# ESP32_Weather.net
KiCad netlist of a schematic drawn in Altium Designer
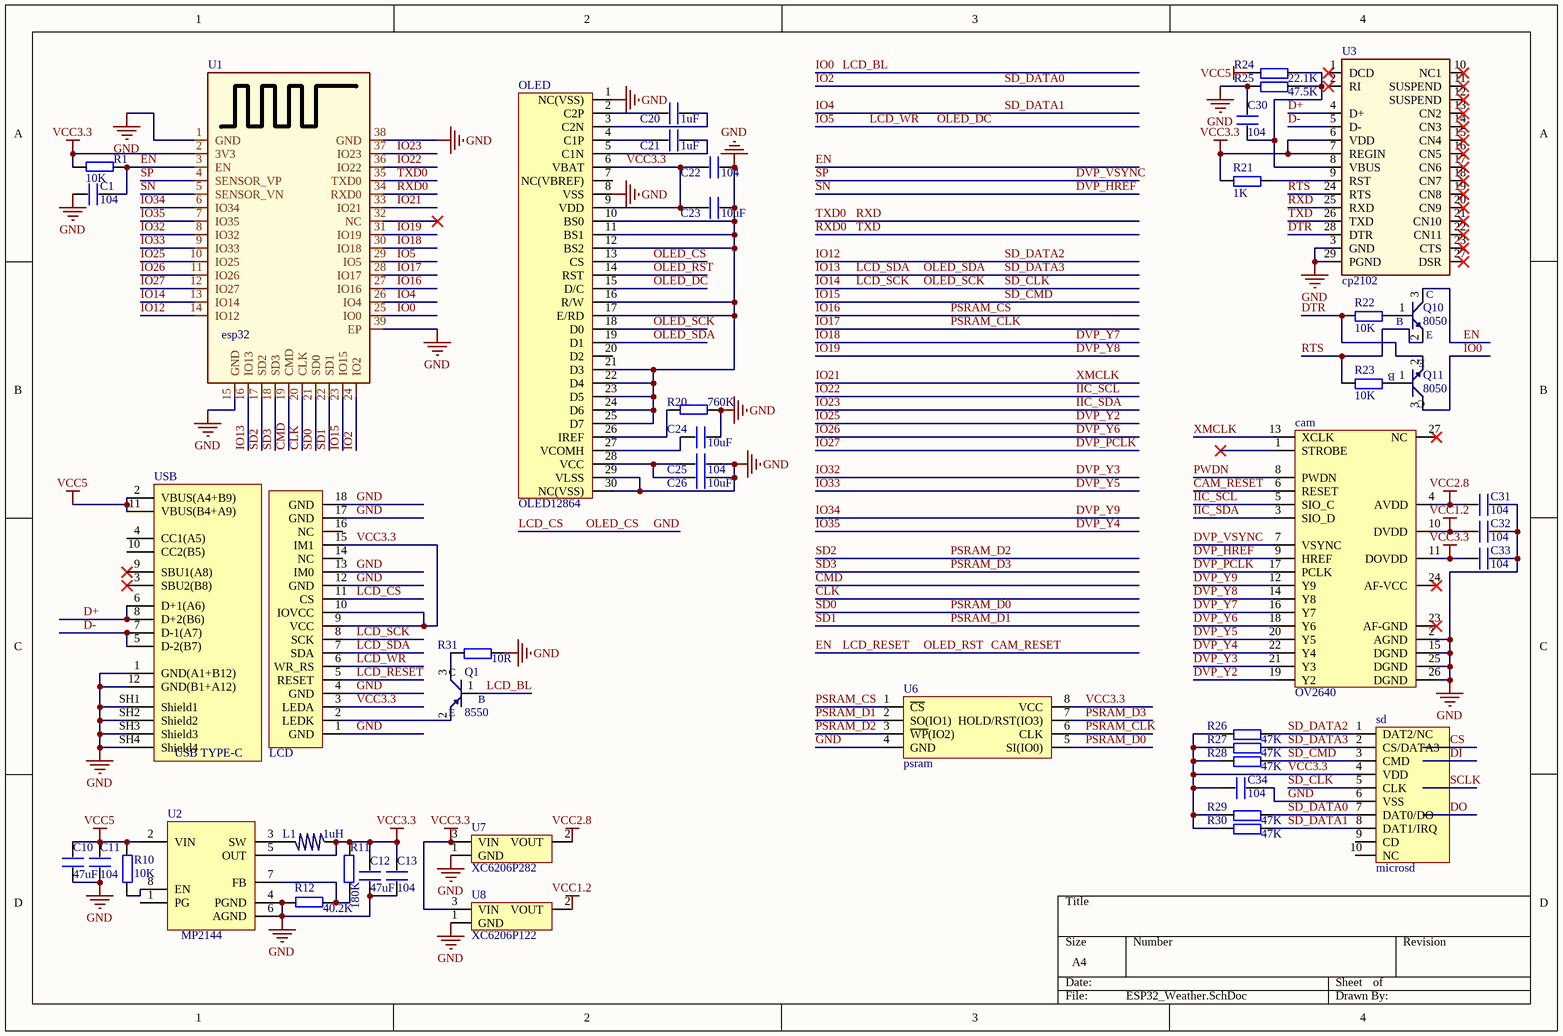
[diagram p0: ESP32_Weather.SchDoc]

(export (version "E")
  (design (tool "Eeschema 10.0.6"))
  (components
    (comp (ref "C1")
      (value "104")
      (footprint "C 0603_L")
      (libsource (lib "WarShip V3 STM32103封装库") (part "C"))
    )
    (comp (ref "C10")
      (value "47uF")
      (footprint "C 0805_L")
      (libsource (lib "WarShip V3 STM32103封装库") (part "C"))
    )
    (comp (ref "C11")
      (value "104")
      (footprint "C 0603_L")
      (libsource (lib "WarShip V3 STM32103封装库") (part "C"))
    )
    (comp (ref "C12")
      (value "47uF")
      (footprint "C 0805_L")
      (libsource (lib "WarShip V3 STM32103封装库") (part "C"))
    )
    (comp (ref "C13")
      (value "104")
      (footprint "C 0603_L")
      (libsource (lib "WarShip V3 STM32103封装库") (part "C"))
    )
    (comp (ref "C20")
      (value "1uF")
      (footprint "C 0603_L")
      (libsource (lib "WarShip V3 STM32103封装库") (part "C"))
    )
    (comp (ref "C21")
      (value "1uF")
      (footprint "C 0603_L")
      (libsource (lib "WarShip V3 STM32103封装库") (part "C"))
    )
    (comp (ref "C22")
      (value "104")
      (footprint "C 0603_L")
      (libsource (lib "WarShip V3 STM32103封装库") (part "C"))
    )
    (comp (ref "C23")
      (value "10uF")
      (footprint "C 0603_L")
      (libsource (lib "WarShip V3 STM32103封装库") (part "C"))
    )
    (comp (ref "C24")
      (value "10uF")
      (footprint "C 0603_L")
      (libsource (lib "WarShip V3 STM32103封装库") (part "C"))
    )
    (comp (ref "C25")
      (value "104")
      (footprint "C 0603_L")
      (libsource (lib "WarShip V3 STM32103封装库") (part "C"))
    )
    (comp (ref "C26")
      (value "10uF")
      (footprint "C 0603_L")
      (libsource (lib "WarShip V3 STM32103封装库") (part "C"))
    )
    (comp (ref "C30")
      (value "104")
      (footprint "C 0603_L")
      (libsource (lib "WarShip V3 STM32103封装库") (part "C"))
    )
    (comp (ref "C31")
      (value "104")
      (footprint "C 0603_L")
      (libsource (lib "WarShip V3 STM32103封装库") (part "C"))
    )
    (comp (ref "C32")
      (value "104")
      (footprint "C 0603_L")
      (libsource (lib "WarShip V3 STM32103封装库") (part "C"))
    )
    (comp (ref "C33")
      (value "104")
      (footprint "C 0603_L")
      (libsource (lib "WarShip V3 STM32103封装库") (part "C"))
    )
    (comp (ref "C34")
      (value "104")
      (footprint "C 0603_L")
      (libsource (lib "WarShip V3 STM32103封装库") (part "C"))
    )
    (comp (ref "cam")
      (value "OV2640")
      (footprint "OV5640")
      (libsource (lib "stm32f767igt6simple") (part "OV5640"))
    )
    (comp (ref "L1") (value "1uH") (footprint "NR3015") (libsource (lib "MiniFly ") (part "L")))
    (comp (ref "LCD")
      (value "LCD-TFT-H13TS38A")
      (footprint "TFT-H13TS43B")
      (description "LCD,TFT,1.3'240*240,禹龙")
      (libsource (lib "Pandora_STM32L4_Board_V2.4") (part "LCD-TFT-H13TS38A"))
    )
    (comp (ref "OLED")
      (value "OLED12864")
      (footprint "OLED_0.96")
      (libsource (lib "OLED模块封装库") (part "OLED12864"))
    )
    (comp (ref "Q1") (value "8550") (footprint "SOT23-3L") (libsource (lib "ESP32_Weather") (part "8550PNP")))
    (comp (ref "Q10")
      (value "8050")
      (footprint "SOT23-3L")
      (libsource (lib "ESP32_Weather") (part "8050NPN"))
    )
    (comp (ref "Q11")
      (value "8050")
      (footprint "SOT23-3L")
      (libsource (lib "ESP32_Weather") (part "8050NPN"))
    )
    (comp (ref "R1") (value "10K") (footprint "R 0603_L") (libsource (lib "阿波罗STM32F4&F7底板封装库") (part "R")))
    (comp (ref "R10") (value "10K") (footprint "R 0603_L") (libsource (lib "阿波罗STM32F4&F7底板封装库") (part "R")))
    (comp (ref "R11") (value "180K") (footprint "R 0603_L") (libsource (lib "电阻-电容-电感") (part "R")))
    (comp (ref "R12") (value "40.2K") (footprint "R 0603_L") (libsource (lib "电阻-电容-电感") (part "R")))
    (comp (ref "R20")
      (value "760K")
      (footprint "R 0603_L")
      (libsource (lib "WarShip V3 STM32103封装库") (part "R"))
    )
    (comp (ref "R21")
      (value "1K")
      (footprint "R 0603_L")
      (libsource (lib "WarShip V3 STM32103封装库") (part "R"))
    )
    (comp (ref "R22")
      (value "10K")
      (footprint "R 0603_L")
      (libsource (lib "WarShip V3 STM32103封装库") (part "R"))
    )
    (comp (ref "R23")
      (value "10K")
      (footprint "R 0603_L")
      (libsource (lib "WarShip V3 STM32103封装库") (part "R"))
    )
    (comp (ref "R24")
      (value "22.1K")
      (footprint "R 0603_L")
      (libsource (lib "WarShip V3 STM32103封装库") (part "R"))
    )
    (comp (ref "R25")
      (value "47.5K")
      (footprint "R 0603_L")
      (libsource (lib "WarShip V3 STM32103封装库") (part "R"))
    )
    (comp (ref "R26")
      (value "47K")
      (footprint "R 0603_L")
      (libsource (lib "WarShip V3 STM32103封装库") (part "R"))
    )
    (comp (ref "R27")
      (value "47K")
      (footprint "R 0603_L")
      (libsource (lib "WarShip V3 STM32103封装库") (part "R"))
    )
    (comp (ref "R28")
      (value "47K")
      (footprint "R 0603_L")
      (libsource (lib "WarShip V3 STM32103封装库") (part "R"))
    )
    (comp (ref "R29")
      (value "47K")
      (footprint "R 0603_L")
      (libsource (lib "WarShip V3 STM32103封装库") (part "R"))
    )
    (comp (ref "R30")
      (value "47K")
      (footprint "R 0603_L")
      (libsource (lib "WarShip V3 STM32103封装库") (part "R"))
    )
    (comp (ref "R31")
      (value "10R")
      (footprint "R 0603_L")
      (libsource (lib "WarShip V3 STM32103封装库") (part "R"))
    )
    (comp (ref "sd")
      (value "microsd")
      (footprint "microsd3")
      (libsource (lib "stm32f767igt6simple") (part "microsd"))
    )
    (comp (ref "U1") (value "esp32") (footprint "ESP32") (libsource (lib "ESP32_Weather") (part "ESP32")))
    (comp (ref "U2") (value "MP2144") (footprint "SOT23-8L") (libsource (lib "LDO和DCDC") (part "MP2144")))
    (comp (ref "U3")
      (value "cp2102")
      (footprint "QFN28 5x5_N")
      (libsource (lib "ESP32_Weather") (part "CP2102"))
    )
    (comp (ref "U6")
      (value "psram")
      (footprint "SOP8_L")
      (libsource (lib "stm32f767igt6simple") (part "w25q256"))
    )
    (comp (ref "U7")
      (value "XC6206P282")
      (footprint "SOT23-3L")
      (description "LDO,SOT23,1.2~5.0V")
      (libsource (lib "ATK-OV5640摄像头模块封装库") (part "XC6206"))
    )
    (comp (ref "U8")
      (value "XC6206P122")
      (footprint "SOT23-3L")
      (description "LDO,SOT23,1.2~5.0V")
      (libsource (lib "ATK-OV5640摄像头模块封装库") (part "XC6206"))
    )
    (comp (ref "USB")
      (value "USB TypeC")
      (footprint "USB Type-C")
      (description "12P TypeC 母座")
      (libsource (lib "接口类") (part "USB Type-C"))
    )
  )
  (nets
    (net (code "1") (name "/CAM_RESET") (class "Default")
      (node (ref "C1") (pin "2") (pintype "passive"))
      (node (ref "LCD") (pin "5") (pinfunction "RESET_5") (pintype "passive"))
      (node (ref "OLED") (pin "14") (pinfunction "RST_14") (pintype "passive"))
      (node (ref "Q10") (pin "3") (pinfunction "C_3") (pintype "passive"))
      (node (ref "R1") (pin "1") (pintype "passive"))
      (node (ref "U1") (pin "3") (pinfunction "EN_3") (pintype "passive"))
      (node (ref "cam") (pin "6") (pinfunction "RESET_6") (pintype "passive"))
    )
    (net (code "2") (name "/CLK") (class "Default")
      (node (ref "U1") (pin "20") (pinfunction "CLK_20") (pintype "passive"))
    )
    (net (code "3") (name "/CMD") (class "Default")
      (node (ref "U1") (pin "19") (pinfunction "CMD_19") (pintype "passive"))
    )
    (net (code "5") (name "/D+") (class "Default")
      (node (ref "U3") (pin "4") (pinfunction "D+_4") (pintype "passive"))
      (node (ref "USB") (pin "6") (pinfunction "D+1(A6)_6") (pintype "passive"))
      (node (ref "USB") (pin "8") (pinfunction "D+2(B6)_8") (pintype "passive"))
    )
    (net (code "6") (name "/D-") (class "Default")
      (node (ref "U3") (pin "5") (pinfunction "D-_5") (pintype "passive"))
      (node (ref "USB") (pin "5") (pinfunction "D-2(B7)_5") (pintype "passive"))
      (node (ref "USB") (pin "7") (pinfunction "D-1(A7)_7") (pintype "passive"))
    )
    (net (code "9") (name "/DTR") (class "Default")
      (node (ref "Q11") (pin "2") (pinfunction "E_2") (pintype "passive"))
      (node (ref "R22") (pin "1") (pintype "passive"))
      (node (ref "U3") (pin "28") (pinfunction "DTR_28") (pintype "passive"))
    )
    (net (code "10") (name "/DVP_HREF") (class "Default")
      (node (ref "U1") (pin "5") (pinfunction "SENSOR_VN_5") (pintype "passive"))
      (node (ref "cam") (pin "9") (pinfunction "HREF_9") (pintype "passive"))
    )
    (net (code "11") (name "/DVP_PCLK") (class "Default")
      (node (ref "U1") (pin "12") (pinfunction "IO27_12") (pintype "passive"))
      (node (ref "cam") (pin "17") (pinfunction "PCLK_17") (pintype "passive"))
    )
    (net (code "12") (name "/DVP_VSYNC") (class "Default")
      (node (ref "U1") (pin "4") (pinfunction "SENSOR_VP_4") (pintype "passive"))
      (node (ref "cam") (pin "7") (pinfunction "VSYNC_7") (pintype "passive"))
    )
    (net (code "13") (name "/DVP_Y2") (class "Default")
      (node (ref "U1") (pin "10") (pinfunction "IO25_10") (pintype "passive"))
      (node (ref "cam") (pin "19") (pinfunction "Y2_19") (pintype "passive"))
    )
    (net (code "14") (name "/DVP_Y3") (class "Default")
      (node (ref "U1") (pin "8") (pinfunction "IO32_8") (pintype "passive"))
      (node (ref "cam") (pin "21") (pinfunction "Y3_21") (pintype "passive"))
    )
    (net (code "15") (name "/DVP_Y4") (class "Default")
      (node (ref "U1") (pin "7") (pinfunction "IO35_7") (pintype "passive"))
      (node (ref "cam") (pin "22") (pinfunction "Y4_22") (pintype "passive"))
    )
    (net (code "16") (name "/DVP_Y5") (class "Default")
      (node (ref "U1") (pin "9") (pinfunction "IO33_9") (pintype "passive"))
      (node (ref "cam") (pin "20") (pinfunction "Y5_20") (pintype "passive"))
    )
    (net (code "17") (name "/DVP_Y6") (class "Default")
      (node (ref "U1") (pin "11") (pinfunction "IO26_11") (pintype "passive"))
      (node (ref "cam") (pin "18") (pinfunction "Y6_18") (pintype "passive"))
    )
    (net (code "18") (name "/DVP_Y7") (class "Default")
      (node (ref "U1") (pin "30") (pinfunction "IO18_30") (pintype "passive"))
      (node (ref "cam") (pin "16") (pinfunction "Y7_16") (pintype "passive"))
    )
    (net (code "19") (name "/DVP_Y8") (class "Default")
      (node (ref "U1") (pin "31") (pinfunction "IO19_31") (pintype "passive"))
      (node (ref "cam") (pin "14") (pinfunction "Y8_14") (pintype "passive"))
    )
    (net (code "20") (name "/DVP_Y9") (class "Default")
      (node (ref "U1") (pin "6") (pinfunction "IO34_6") (pintype "passive"))
      (node (ref "cam") (pin "12") (pinfunction "Y9_12") (pintype "passive"))
    )
    (net (code "21") (name "/IIC_SCL") (class "Default")
      (node (ref "U1") (pin "36") (pinfunction "IO22_36") (pintype "passive"))
      (node (ref "cam") (pin "5") (pinfunction "SIO_C_5") (pintype "passive"))
    )
    (net (code "22") (name "/IIC_SDA") (class "Default")
      (node (ref "U1") (pin "37") (pinfunction "IO23_37") (pintype "passive"))
      (node (ref "cam") (pin "3") (pinfunction "SIO_D_3") (pintype "passive"))
    )
    (net (code "23") (name "/IO0") (class "Default")
      (node (ref "Q1") (pin "1") (pinfunction "B_1") (pintype "passive"))
      (node (ref "Q11") (pin "3") (pinfunction "C_3") (pintype "passive"))
      (node (ref "U1") (pin "25") (pinfunction "IO0_25") (pintype "passive"))
    )
    (net (code "24") (name "/IO2") (class "Default")
      (node (ref "R29") (pin "2") (pintype "passive"))
      (node (ref "U1") (pin "24") (pinfunction "IO2_24") (pintype "passive"))
      (node (ref "sd") (pin "7") (pinfunction "DAT0/DO_7") (pintype "passive"))
    )
    (net (code "25") (name "/IO4") (class "Default")
      (node (ref "R30") (pin "2") (pintype "passive"))
      (node (ref "U1") (pin "26") (pinfunction "IO4_26") (pintype "passive"))
      (node (ref "sd") (pin "8") (pinfunction "DAT1/IRQ_8") (pintype "passive"))
    )
    (net (code "26") (name "/IO5") (class "Default")
      (node (ref "LCD") (pin "6") (pinfunction "WR_RS_6") (pintype "passive"))
      (node (ref "OLED") (pin "15") (pinfunction "D/C_15") (pintype "passive"))
      (node (ref "U1") (pin "29") (pinfunction "IO5_29") (pintype "passive"))
    )
    (net (code "27") (name "/IO12") (class "Default")
      (node (ref "R26") (pin "2") (pintype "passive"))
      (node (ref "U1") (pin "14") (pinfunction "IO12_14") (pintype "passive"))
      (node (ref "sd") (pin "1") (pinfunction "DAT2/NC_1") (pintype "passive"))
    )
    (net (code "28") (name "/IO13") (class "Default")
      (node (ref "LCD") (pin "7") (pinfunction "SDA_7") (pintype "passive"))
      (node (ref "OLED") (pin "19") (pinfunction "D1_19") (pintype "passive"))
      (node (ref "R27") (pin "2") (pintype "passive"))
      (node (ref "U1") (pin "16") (pinfunction "IO13_16") (pintype "passive"))
      (node (ref "sd") (pin "2") (pinfunction "CS/DATA3_2") (pintype "passive"))
    )
    (net (code "29") (name "/IO14") (class "Default")
      (node (ref "LCD") (pin "8") (pinfunction "SCK_8") (pintype "passive"))
      (node (ref "OLED") (pin "18") (pinfunction "D0_18") (pintype "passive"))
      (node (ref "U1") (pin "13") (pinfunction "IO14_13") (pintype "passive"))
      (node (ref "sd") (pin "5") (pinfunction "CLK_5") (pintype "passive"))
    )
    (net (code "30") (name "/IO15") (class "Default")
      (node (ref "R28") (pin "2") (pintype "passive"))
      (node (ref "U1") (pin "23") (pinfunction "IO15_23") (pintype "passive"))
      (node (ref "sd") (pin "3") (pinfunction "CMD_3") (pintype "passive"))
    )
    (net (code "31") (name "/IO16") (class "Default")
      (node (ref "U1") (pin "27") (pinfunction "IO16_27") (pintype "passive"))
      (node (ref "U6") (pin "1") (pinfunction "~{CS}_1") (pintype "passive"))
    )
    (net (code "32") (name "/IO17") (class "Default")
      (node (ref "U1") (pin "28") (pinfunction "IO17_28") (pintype "passive"))
      (node (ref "U6") (pin "6") (pinfunction "CLK_6") (pintype "passive"))
    )
    (net (code "33") (name "/IO21") (class "Default")
      (node (ref "U1") (pin "33") (pinfunction "IO21_33") (pintype "passive"))
      (node (ref "cam") (pin "13") (pinfunction "XCLK_13") (pintype "passive"))
    )
    (net (code "34") (name "/PSRAM_D0") (class "Default")
      (node (ref "U1") (pin "21") (pinfunction "SD0_21") (pintype "passive"))
      (node (ref "U6") (pin "5") (pinfunction "SI(IO0)_5") (pintype "power_in"))
    )
    (net (code "35") (name "/PSRAM_D1") (class "Default")
      (node (ref "U1") (pin "22") (pinfunction "SD1_22") (pintype "passive"))
      (node (ref "U6") (pin "2") (pinfunction "SO(IO1)_2") (pintype "passive"))
    )
    (net (code "36") (name "/PSRAM_D2") (class "Default")
      (node (ref "U1") (pin "17") (pinfunction "SD2_17") (pintype "passive"))
      (node (ref "U6") (pin "3") (pinfunction "~{WP}(IO2)_3") (pintype "passive"))
    )
    (net (code "37") (name "/PSRAM_D3") (class "Default")
      (node (ref "U1") (pin "18") (pinfunction "SD3_18") (pintype "passive"))
      (node (ref "U6") (pin "7") (pinfunction "HOLD/RST(IO3)_7") (pintype "power_in"))
    )
    (net (code "38") (name "/PWDN") (class "Default")
      (node (ref "cam") (pin "8") (pinfunction "PWDN_8") (pintype "passive"))
    )
    (net (code "39") (name "/RTS") (class "Default")
      (node (ref "Q10") (pin "2") (pinfunction "E_2") (pintype "passive"))
      (node (ref "R23") (pin "1") (pintype "passive"))
      (node (ref "U3") (pin "24") (pinfunction "RTS_24") (pintype "passive"))
    )
    (net (code "40") (name "/RXD") (class "Default")
      (node (ref "U1") (pin "35") (pinfunction "TXD0_35") (pintype "passive"))
      (node (ref "U3") (pin "25") (pinfunction "RXD_25") (pintype "passive"))
    )
    (net (code "41") (name "/RXD0") (class "Default")
      (node (ref "U1") (pin "34") (pinfunction "RXD0_34") (pintype "passive"))
      (node (ref "U3") (pin "26") (pinfunction "TXD_26") (pintype "passive"))
    )
    (net (code "43") (name "GND") (class "Default")
      (node (ref "C1") (pin "1") (pintype "passive"))
      (node (ref "C10") (pin "1") (pintype "passive"))
      (node (ref "C11") (pin "1") (pintype "passive"))
      (node (ref "C12") (pin "1") (pintype "passive"))
      (node (ref "C13") (pin "1") (pintype "passive"))
      (node (ref "C22") (pin "1") (pintype "passive"))
      (node (ref "C23") (pin "1") (pintype "passive"))
      (node (ref "C24") (pin "1") (pintype "passive"))
      (node (ref "C25") (pin "1") (pintype "passive"))
      (node (ref "C26") (pin "1") (pintype "passive"))
      (node (ref "C30") (pin "1") (pintype "passive"))
      (node (ref "C31") (pin "2") (pintype "passive"))
      (node (ref "C32") (pin "2") (pintype "passive"))
      (node (ref "C33") (pin "2") (pintype "passive"))
      (node (ref "C34") (pin "2") (pintype "passive"))
      (node (ref "LCD") (pin "1") (pinfunction "GND_1") (pintype "passive"))
      (node (ref "LCD") (pin "11") (pinfunction "CS_11") (pintype "passive"))
      (node (ref "LCD") (pin "12") (pinfunction "GND_12") (pintype "passive"))
      (node (ref "LCD") (pin "13") (pinfunction "IM0_13") (pintype "passive"))
      (node (ref "LCD") (pin "17") (pinfunction "GND_17") (pintype "passive"))
      (node (ref "LCD") (pin "18") (pinfunction "GND_18") (pintype "passive"))
      (node (ref "LCD") (pin "4") (pinfunction "GND_4") (pintype "passive"))
      (node (ref "OLED") (pin "1") (pinfunction "NC(VSS)_1") (pintype "passive"))
      (node (ref "OLED") (pin "10") (pinfunction "BS0_10") (pintype "passive"))
      (node (ref "OLED") (pin "11") (pinfunction "BS1_11") (pintype "passive"))
      (node (ref "OLED") (pin "12") (pinfunction "BS2_12") (pintype "passive"))
      (node (ref "OLED") (pin "13") (pinfunction "CS_13") (pintype "passive"))
      (node (ref "OLED") (pin "16") (pinfunction "R/W_16") (pintype "passive"))
      (node (ref "OLED") (pin "17") (pinfunction "E/RD_17") (pintype "passive"))
      (node (ref "OLED") (pin "21") (pinfunction "D3_21") (pintype "passive"))
      (node (ref "OLED") (pin "22") (pinfunction "D4_22") (pintype "passive"))
      (node (ref "OLED") (pin "23") (pinfunction "D5_23") (pintype "passive"))
      (node (ref "OLED") (pin "24") (pinfunction "D6_24") (pintype "passive"))
      (node (ref "OLED") (pin "25") (pinfunction "D7_25") (pintype "passive"))
      (node (ref "OLED") (pin "29") (pinfunction "VLSS_29") (pintype "passive"))
      (node (ref "OLED") (pin "30") (pinfunction "NC(VSS)_30") (pintype "passive"))
      (node (ref "OLED") (pin "8") (pinfunction "VSS_8") (pintype "passive"))
      (node (ref "R12") (pin "2") (pintype "passive"))
      (node (ref "R20") (pin "1") (pintype "passive"))
      (node (ref "R25") (pin "1") (pintype "passive"))
      (node (ref "R31") (pin "2") (pintype "passive"))
      (node (ref "U1") (pin "1") (pinfunction "GND_1") (pintype "passive"))
      (node (ref "U1") (pin "15") (pinfunction "GND_15") (pintype "passive"))
      (node (ref "U1") (pin "38") (pinfunction "GND_38") (pintype "passive"))
      (node (ref "U1") (pin "39") (pinfunction "EP_39") (pintype "passive"))
      (node (ref "U2") (pin "4") (pinfunction "PGND_4") (pintype "passive"))
      (node (ref "U2") (pin "6") (pinfunction "AGND_6") (pintype "passive"))
      (node (ref "U3") (pin "29") (pinfunction "PGND_29") (pintype "passive"))
      (node (ref "U3") (pin "3") (pinfunction "GND_3") (pintype "passive"))
      (node (ref "U6") (pin "4") (pinfunction "GND_4") (pintype "passive"))
      (node (ref "U7") (pin "1") (pinfunction "GND_1") (pintype "passive"))
      (node (ref "U8") (pin "1") (pinfunction "GND_1") (pintype "passive"))
      (node (ref "USB") (pin "1") (pinfunction "GND(A1+B12)_1") (pintype "passive"))
      (node (ref "USB") (pin "12") (pinfunction "GND(B1+A12)_12") (pintype "passive"))
      (node (ref "USB") (pin "SH1") (pinfunction "Shield1_SH1") (pintype "passive"))
      (node (ref "USB") (pin "SH2") (pinfunction "Shield2_SH2") (pintype "passive"))
      (node (ref "USB") (pin "SH3") (pinfunction "Shield3_SH3") (pintype "passive"))
      (node (ref "USB") (pin "SH4") (pinfunction "Shield4_SH4") (pintype "passive"))
      (node (ref "cam") (pin "15") (pinfunction "DGND_15") (pintype "passive"))
      (node (ref "cam") (pin "2") (pinfunction "AGND_2") (pintype "passive"))
      (node (ref "cam") (pin "25") (pinfunction "DGND_25") (pintype "passive"))
      (node (ref "cam") (pin "26") (pinfunction "DGND_26") (pintype "passive"))
      (node (ref "sd") (pin "6") (pinfunction "VSS_6") (pintype "passive"))
    )
    (net (code "44") (name "Net-(LCD-LEDK)") (class "Default")
      (node (ref "LCD") (pin "2") (pinfunction "LEDK_2") (pintype "passive"))
      (node (ref "Q1") (pin "2") (pinfunction "E_2") (pintype "passive"))
    )
    (net (code "45") (name "Net-(OLED-C1N)") (class "Default")
      (node (ref "C21") (pin "1") (pintype "passive"))
      (node (ref "OLED") (pin "5") (pinfunction "C1N_5") (pintype "passive"))
    )
    (net (code "46") (name "Net-(OLED-C1P)") (class "Default")
      (node (ref "C21") (pin "2") (pintype "passive"))
      (node (ref "OLED") (pin "4") (pinfunction "C1P_4") (pintype "passive"))
    )
    (net (code "47") (name "Net-(OLED-C2N)") (class "Default")
      (node (ref "C20") (pin "1") (pintype "passive"))
      (node (ref "OLED") (pin "3") (pinfunction "C2N_3") (pintype "passive"))
    )
    (net (code "48") (name "Net-(OLED-C2P)") (class "Default")
      (node (ref "C20") (pin "2") (pintype "passive"))
      (node (ref "OLED") (pin "2") (pinfunction "C2P_2") (pintype "passive"))
    )
    (net (code "49") (name "Net-(OLED-IREF)") (class "Default")
      (node (ref "OLED") (pin "26") (pinfunction "IREF_26") (pintype "passive"))
      (node (ref "R20") (pin "2") (pintype "passive"))
    )
    (net (code "50") (name "Net-(OLED-VCC)") (class "Default")
      (node (ref "C25") (pin "2") (pintype "passive"))
      (node (ref "C26") (pin "2") (pintype "passive"))
      (node (ref "OLED") (pin "28") (pinfunction "VCC_28") (pintype "passive"))
    )
    (net (code "51") (name "Net-(OLED-VCOMH)") (class "Default")
      (node (ref "C24") (pin "2") (pintype "passive"))
      (node (ref "OLED") (pin "27") (pinfunction "VCOMH_27") (pintype "passive"))
    )
    (net (code "52") (name "Net-(Q1-C)") (class "Default")
      (node (ref "Q1") (pin "3") (pinfunction "C_3") (pintype "passive"))
      (node (ref "R31") (pin "1") (pintype "passive"))
    )
    (net (code "53") (name "Net-(Q10-B)") (class "Default")
      (node (ref "Q10") (pin "1") (pinfunction "B_1") (pintype "passive"))
      (node (ref "R22") (pin "2") (pintype "passive"))
    )
    (net (code "54") (name "Net-(Q11-B)") (class "Default")
      (node (ref "Q11") (pin "1") (pinfunction "B_1") (pintype "passive"))
      (node (ref "R23") (pin "2") (pintype "passive"))
    )
    (net (code "55") (name "Net-(U2-EN)") (class "Default")
      (node (ref "R10") (pin "1") (pintype "passive"))
      (node (ref "U2") (pin "8") (pinfunction "EN_8") (pintype "passive"))
    )
    (net (code "56") (name "Net-(U2-FB)") (class "Default")
      (node (ref "R11") (pin "2") (pintype "passive"))
      (node (ref "R12") (pin "1") (pintype "passive"))
      (node (ref "U2") (pin "7") (pinfunction "FB_7") (pintype "passive"))
    )
    (net (code "57") (name "Net-(U2-SW)") (class "Default")
      (node (ref "L1") (pin "2") (pintype "passive"))
      (node (ref "U2") (pin "3") (pinfunction "SW_3") (pintype "passive"))
    )
    (net (code "58") (name "Net-(U3-RST)") (class "Default")
      (node (ref "R21") (pin "2") (pintype "passive"))
      (node (ref "U3") (pin "9") (pinfunction "RST_9") (pintype "passive"))
    )
    (net (code "59") (name "Net-(U3-VBUS)") (class "Default")
      (node (ref "C30") (pin "2") (pintype "passive"))
      (node (ref "R24") (pin "2") (pintype "passive"))
      (node (ref "R25") (pin "2") (pintype "passive"))
      (node (ref "U3") (pin "8") (pinfunction "VBUS_8") (pintype "passive"))
    )
    (net (code "60") (name "VCC1.2") (class "Default")
      (node (ref "C32") (pin "1") (pintype "passive"))
      (node (ref "U8") (pin "2") (pinfunction "VOUT_2") (pintype "passive"))
      (node (ref "cam") (pin "10") (pinfunction "DVDD_10") (pintype "passive"))
    )
    (net (code "61") (name "VCC2.8") (class "Default")
      (node (ref "C31") (pin "1") (pintype "passive"))
      (node (ref "U7") (pin "2") (pinfunction "VOUT_2") (pintype "passive"))
      (node (ref "cam") (pin "4") (pinfunction "AVDD_4") (pintype "passive"))
    )
    (net (code "62") (name "VCC3.3") (class "Default")
      (node (ref "C12") (pin "2") (pintype "passive"))
      (node (ref "C13") (pin "2") (pintype "passive"))
      (node (ref "C22") (pin "2") (pintype "passive"))
      (node (ref "C23") (pin "2") (pintype "passive"))
      (node (ref "C33") (pin "1") (pintype "passive"))
      (node (ref "C34") (pin "1") (pintype "passive"))
      (node (ref "L1") (pin "1") (pintype "passive"))
      (node (ref "LCD") (pin "10") (pinfunction "IOVCC_10") (pintype "passive"))
      (node (ref "LCD") (pin "15") (pinfunction "IM1_15") (pintype "passive"))
      (node (ref "LCD") (pin "3") (pinfunction "LEDA_3") (pintype "passive"))
      (node (ref "LCD") (pin "9") (pinfunction "VCC_9") (pintype "passive"))
      (node (ref "OLED") (pin "6") (pinfunction "VBAT_6") (pintype "passive"))
      (node (ref "OLED") (pin "9") (pinfunction "VDD_9") (pintype "passive"))
      (node (ref "R1") (pin "2") (pintype "passive"))
      (node (ref "R11") (pin "1") (pintype "passive"))
      (node (ref "R21") (pin "1") (pintype "passive"))
      (node (ref "R26") (pin "1") (pintype "passive"))
      (node (ref "R27") (pin "1") (pintype "passive"))
      (node (ref "R28") (pin "1") (pintype "passive"))
      (node (ref "R29") (pin "1") (pintype "passive"))
      (node (ref "R30") (pin "1") (pintype "passive"))
      (node (ref "U1") (pin "2") (pinfunction "3V3_2") (pintype "passive"))
      (node (ref "U2") (pin "5") (pinfunction "OUT_5") (pintype "passive"))
      (node (ref "U3") (pin "6") (pinfunction "VDD_6") (pintype "passive"))
      (node (ref "U3") (pin "7") (pinfunction "REGIN_7") (pintype "passive"))
      (node (ref "U6") (pin "8") (pinfunction "VCC_8") (pintype "passive"))
      (node (ref "U7") (pin "3") (pinfunction "VIN_3") (pintype "passive"))
      (node (ref "U8") (pin "3") (pinfunction "VIN_3") (pintype "passive"))
      (node (ref "cam") (pin "11") (pinfunction "DOVDD_11") (pintype "passive"))
      (node (ref "sd") (pin "4") (pinfunction "VDD_4") (pintype "passive"))
    )
    (net (code "63") (name "VCC5") (class "Default")
      (node (ref "C10") (pin "2") (pintype "passive"))
      (node (ref "C11") (pin "2") (pintype "passive"))
      (node (ref "R10") (pin "2") (pintype "passive"))
      (node (ref "R24") (pin "1") (pintype "passive"))
      (node (ref "U2") (pin "2") (pinfunction "VIN_2") (pintype "passive"))
      (node (ref "USB") (pin "11") (pinfunction "VBUS(B4+A9)_11") (pintype "passive"))
      (node (ref "USB") (pin "2") (pinfunction "VBUS(A4+B9)_2") (pintype "passive"))
    )
    (net (code "64") (name "unconnected-(LCD-NC-Pad14)") (class "Default")
      (node (ref "LCD") (pin "14") (pinfunction "NC_14") (pintype "passive"))
    )
    (net (code "65") (name "unconnected-(LCD-NC-Pad16)") (class "Default")
      (node (ref "LCD") (pin "16") (pinfunction "NC_16") (pintype "passive"))
    )
    (net (code "66") (name "unconnected-(OLED-D2-Pad20)") (class "Default")
      (node (ref "OLED") (pin "20") (pinfunction "D2_20") (pintype "passive"))
    )
    (net (code "67") (name "unconnected-(OLED-NC(VBREF)-Pad7)") (class "Default")
      (node (ref "OLED") (pin "7") (pinfunction "NC(VBREF)_7") (pintype "passive"))
    )
    (net (code "68") (name "unconnected-(U1-NC-Pad32)") (class "Default")
      (node (ref "U1") (pin "32") (pinfunction "NC_32") (pintype "passive+no_connect"))
    )
    (net (code "69") (name "unconnected-(U2-PG-Pad1)") (class "Default")
      (node (ref "U2") (pin "1") (pinfunction "PG_1") (pintype "passive"))
    )
    (net (code "70") (name "unconnected-(U3-CN2-Pad13)") (class "Default")
      (node (ref "U3") (pin "13") (pinfunction "CN2_13") (pintype "passive+no_connect"))
    )
    (net (code "71") (name "unconnected-(U3-CN3-Pad14)") (class "Default")
      (node (ref "U3") (pin "14") (pinfunction "CN3_14") (pintype "passive+no_connect"))
    )
    (net (code "72") (name "unconnected-(U3-CN4-Pad15)") (class "Default")
      (node (ref "U3") (pin "15") (pinfunction "CN4_15") (pintype "passive+no_connect"))
    )
    (net (code "73") (name "unconnected-(U3-CN5-Pad16)") (class "Default")
      (node (ref "U3") (pin "16") (pinfunction "CN5_16") (pintype "passive+no_connect"))
    )
    (net (code "74") (name "unconnected-(U3-CN6-Pad17)") (class "Default")
      (node (ref "U3") (pin "17") (pinfunction "CN6_17") (pintype "passive+no_connect"))
    )
    (net (code "75") (name "unconnected-(U3-CN7-Pad18)") (class "Default")
      (node (ref "U3") (pin "18") (pinfunction "CN7_18") (pintype "passive+no_connect"))
    )
    (net (code "76") (name "unconnected-(U3-CN8-Pad19)") (class "Default")
      (node (ref "U3") (pin "19") (pinfunction "CN8_19") (pintype "passive+no_connect"))
    )
    (net (code "77") (name "unconnected-(U3-CN9-Pad20)") (class "Default")
      (node (ref "U3") (pin "20") (pinfunction "CN9_20") (pintype "passive+no_connect"))
    )
    (net (code "78") (name "unconnected-(U3-CN10-Pad21)") (class "Default")
      (node (ref "U3") (pin "21") (pinfunction "CN10_21") (pintype "passive+no_connect"))
    )
    (net (code "79") (name "unconnected-(U3-CN11-Pad22)") (class "Default")
      (node (ref "U3") (pin "22") (pinfunction "CN11_22") (pintype "passive+no_connect"))
    )
    (net (code "80") (name "unconnected-(U3-CTS-Pad23)") (class "Default")
      (node (ref "U3") (pin "23") (pinfunction "CTS_23") (pintype "passive+no_connect"))
    )
    (net (code "81") (name "unconnected-(U3-DCD-Pad1)") (class "Default")
      (node (ref "U3") (pin "1") (pinfunction "DCD_1") (pintype "passive+no_connect"))
    )
    (net (code "82") (name "unconnected-(U3-DSR-Pad27)") (class "Default")
      (node (ref "U3") (pin "27") (pinfunction "DSR_27") (pintype "passive+no_connect"))
    )
    (net (code "83") (name "unconnected-(U3-NC1-Pad10)") (class "Default")
      (node (ref "U3") (pin "10") (pinfunction "NC1_10") (pintype "passive+no_connect"))
    )
    (net (code "84") (name "unconnected-(U3-RI-Pad2)") (class "Default")
      (node (ref "U3") (pin "2") (pinfunction "RI_2") (pintype "passive+no_connect"))
    )
    (net (code "85") (name "unconnected-(U3-SUSPEND-Pad11)") (class "Default")
      (node (ref "U3") (pin "11") (pinfunction "SUSPEND_11") (pintype "passive+no_connect"))
    )
    (net (code "86") (name "unconnected-(U3-SUSPEND-Pad12)") (class "Default")
      (node (ref "U3") (pin "12") (pinfunction "SUSPEND_12") (pintype "passive+no_connect"))
    )
    (net (code "87") (name "unconnected-(USB-CC1(A5)-Pad4)") (class "Default")
      (node (ref "USB") (pin "4") (pinfunction "CC1(A5)_4") (pintype "passive"))
    )
    (net (code "88") (name "unconnected-(USB-CC2(B5)-Pad10)") (class "Default")
      (node (ref "USB") (pin "10") (pinfunction "CC2(B5)_10") (pintype "passive"))
    )
    (net (code "89") (name "unconnected-(USB-SBU1(A8)-Pad9)") (class "Default")
      (node (ref "USB") (pin "9") (pinfunction "SBU1(A8)_9") (pintype "passive+no_connect"))
    )
    (net (code "90") (name "unconnected-(USB-SBU2(B8)-Pad3)") (class "Default")
      (node (ref "USB") (pin "3") (pinfunction "SBU2(B8)_3") (pintype "passive+no_connect"))
    )
    (net (code "91") (name "unconnected-(cam-AF-GND-Pad23)") (class "Default")
      (node (ref "cam") (pin "23") (pinfunction "AF-GND_23") (pintype "passive+no_connect"))
    )
    (net (code "92") (name "unconnected-(cam-AF-VCC-Pad24)") (class "Default")
      (node (ref "cam") (pin "24") (pinfunction "AF-VCC_24") (pintype "passive+no_connect"))
    )
    (net (code "93") (name "unconnected-(cam-NC-Pad27)") (class "Default")
      (node (ref "cam") (pin "27") (pinfunction "NC_27") (pintype "passive+no_connect"))
    )
    (net (code "94") (name "unconnected-(cam-STROBE-Pad1)") (class "Default")
      (node (ref "cam") (pin "1") (pinfunction "STROBE_1") (pintype "passive+no_connect"))
    )
    (net (code "95") (name "unconnected-(sd-CD-Pad9)") (class "Default")
      (node (ref "sd") (pin "9") (pinfunction "CD_9") (pintype "passive"))
    )
    (net (code "96") (name "unconnected-(sd-NC-Pad10)") (class "Default")
      (node (ref "sd") (pin "10") (pinfunction "NC_10") (pintype "passive"))
    )
  )
)
